# match_best.net
KiCad netlist of a schematic drawn in EAGLE
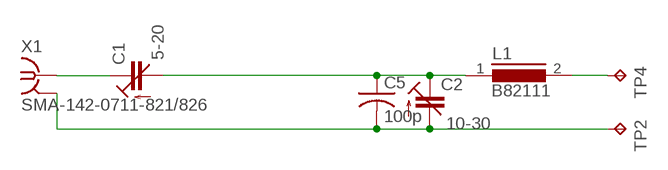
[diagram p0: schematic, sheet 1]

(export (version "E")
  (design (tool "Eeschema 10.0.6"))
  (components
    (comp (ref "C1")
      (value "5-20")
      (footprint "eagle-import:SGC3S")
      (libsource (lib "eagle-import") (part "C-TRIMM"))
    )
    (comp (ref "C2")
      (value "10-30")
      (footprint "eagle-import:SGC3S")
      (libsource (lib "eagle-import") (part "C-TRIMM"))
    )
    (comp (ref "C5")
      (value "100p")
      (footprint "eagle-import:1111")
      (libsource (lib "eagle-import") (part "C-US"))
    )
    (comp (ref "L1")
      (value "B82111")
      (footprint "eagle-import:SUKW1-30")
      (libsource (lib "eagle-import") (part "B82111"))
    )
    (comp (ref "TP2")
      (value "TPPAD1-13Y")
      (footprint "eagle-import:P1-13Y")
      (libsource (lib "eagle-import") (part "TPPAD1-13Y"))
    )
    (comp (ref "TP4")
      (value "TPPAD1-13Y")
      (footprint "eagle-import:P1-13Y")
      (libsource (lib "eagle-import") (part "TPPAD1-13Y"))
    )
    (comp (ref "X1")
      (value "SMA-142-0711-821/826")
      (footprint "eagle-import:J502-ND-142-0711-821_826")
      (fields (field (name "MF") "JOHNSON COMPONENTS") (field (name "MPN") "142-0711-821"))
      (libsource (lib "eagle-import") (part "SMA-142-0711-821/826"))
    )
  )
  (nets
    (net (code "1") (name "Net-(C1-A)") (class "Default")
      (node (ref "C1") (pin "P$1") (pinfunction "A_P$1") (pintype "passive"))
      (node (ref "C2") (pin "P$2") (pinfunction "E_P$2") (pintype "passive"))
      (node (ref "C5") (pin "P$1") (pinfunction "1_P$1") (pintype "passive"))
      (node (ref "L1") (pin "1") (pinfunction "1_1") (pintype "passive"))
    )
    (net (code "2") (name "Net-(C1-E)") (class "Default")
      (node (ref "C1") (pin "P$2") (pinfunction "E_P$2") (pintype "passive"))
      (node (ref "X1") (pin "1") (pinfunction "1_1") (pintype "passive"))
    )
    (net (code "3") (name "Net-(C2-A)") (class "Default")
      (node (ref "C2") (pin "P$1") (pinfunction "A_P$1") (pintype "passive"))
      (node (ref "C5") (pin "P$2") (pinfunction "2_P$2") (pintype "passive"))
      (node (ref "TP2") (pin "TP") (pinfunction "TP_TP") (pintype "input"))
      (node (ref "X1") (pin "G@1") (pinfunction "2_G@1") (pintype "passive"))
      (node (ref "X1") (pin "G@2") (pinfunction "2_G@2") (pintype "passive"))
      (node (ref "X1") (pin "G@3") (pinfunction "2_G@3") (pintype "passive"))
      (node (ref "X1") (pin "G@4") (pinfunction "2_G@4") (pintype "passive"))
    )
    (net (code "4") (name "Net-(L1-Pad2)") (class "Default")
      (node (ref "L1") (pin "2") (pinfunction "2_2") (pintype "passive"))
      (node (ref "TP4") (pin "TP") (pinfunction "TP_TP") (pintype "input"))
    )
  )
)
